# Shield_Master.net
KiCad netlist of a schematic drawn in EAGLE
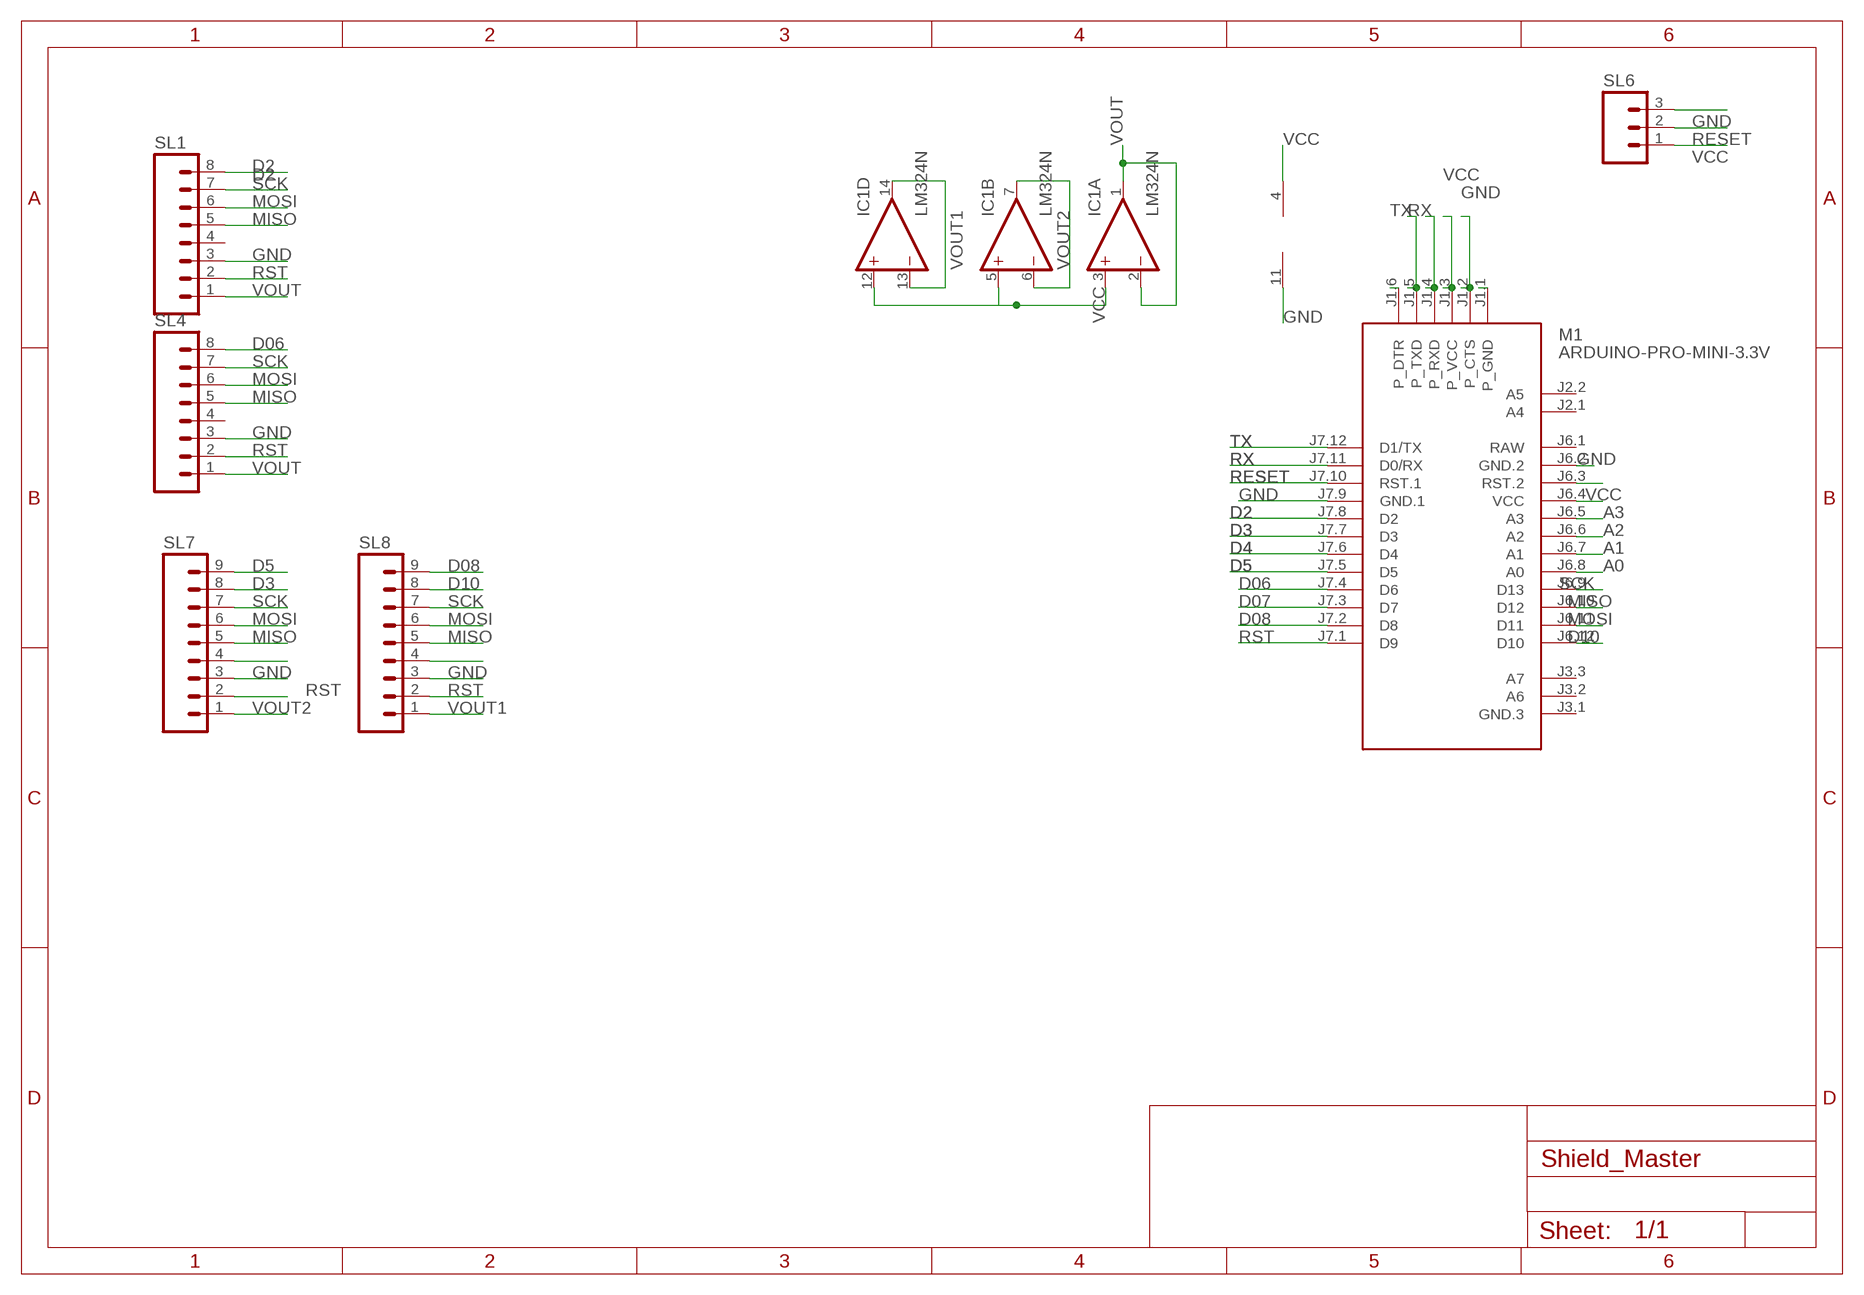
[diagram p0: schematic, sheet 1]

(export (version "E")
  (design (tool "Eeschema 10.0.6"))
  (components
    (comp (ref "IC1")
      (value "LM324N")
      (footprint "eagle-import:DIL14")
      (libsource (lib "eagle-import") (part "LM324N"))
    )
    (comp (ref "M1")
      (value "ARDUINO-PRO-MINI-3.3V")
      (footprint "eagle-import:ARDUINO-PRO-MINI")
      (libsource (lib "eagle-import") (part "ARDUINO-PRO-MINI-3.3V"))
    )
    (comp (ref "SL1")
      (value "M08")
      (footprint "eagle-import:08P")
      (libsource (lib "eagle-import") (part "M08"))
    )
    (comp (ref "SL4")
      (value "M08")
      (footprint "eagle-import:08P")
      (libsource (lib "eagle-import") (part "M08"))
    )
    (comp (ref "SL6")
      (value "M03")
      (footprint "eagle-import:03P")
      (libsource (lib "eagle-import") (part "M03"))
    )
    (comp (ref "SL7")
      (value "M09")
      (footprint "eagle-import:09P")
      (libsource (lib "eagle-import") (part "M09"))
    )
    (comp (ref "SL8")
      (value "M09")
      (footprint "eagle-import:09P")
      (libsource (lib "eagle-import") (part "M09"))
    )
  )
  (nets
    (net (code "1") (name "/A0") (class "Default")
      (node (ref "M1") (pin "J6.8") (pinfunction "A0_J6.8") (pintype "bidirectional"))
    )
    (net (code "2") (name "/A1") (class "Default")
      (node (ref "M1") (pin "J6.7") (pinfunction "A1_J6.7") (pintype "bidirectional"))
    )
    (net (code "3") (name "/A2") (class "Default")
      (node (ref "M1") (pin "J6.6") (pinfunction "A2_J6.6") (pintype "bidirectional"))
    )
    (net (code "4") (name "/A3") (class "Default")
      (node (ref "M1") (pin "J6.5") (pinfunction "A3_J6.5") (pintype "bidirectional"))
    )
    (net (code "5") (name "/D2") (class "Default")
      (node (ref "M1") (pin "J7.8") (pinfunction "D2_J7.8") (pintype "bidirectional"))
      (node (ref "SL1") (pin "8") (pinfunction "8_8") (pintype "passive"))
    )
    (net (code "6") (name "/D3") (class "Default")
      (node (ref "M1") (pin "J7.7") (pinfunction "D3_J7.7") (pintype "bidirectional"))
      (node (ref "SL7") (pin "8") (pinfunction "8_8") (pintype "passive"))
    )
    (net (code "7") (name "/D4") (class "Default")
      (node (ref "M1") (pin "J7.6") (pinfunction "D4_J7.6") (pintype "bidirectional"))
    )
    (net (code "8") (name "/D5") (class "Default")
      (node (ref "M1") (pin "J7.5") (pinfunction "D5_J7.5") (pintype "bidirectional"))
      (node (ref "SL7") (pin "9") (pinfunction "9_9") (pintype "passive"))
    )
    (net (code "9") (name "/D06") (class "Default")
      (node (ref "M1") (pin "J7.4") (pinfunction "D6_J7.4") (pintype "bidirectional"))
      (node (ref "SL4") (pin "8") (pinfunction "8_8") (pintype "passive"))
    )
    (net (code "10") (name "/D07") (class "Default")
      (node (ref "M1") (pin "J7.3") (pinfunction "D7_J7.3") (pintype "bidirectional"))
    )
    (net (code "11") (name "/D08") (class "Default")
      (node (ref "M1") (pin "J7.2") (pinfunction "D8_J7.2") (pintype "bidirectional"))
      (node (ref "SL8") (pin "9") (pinfunction "9_9") (pintype "passive"))
    )
    (net (code "12") (name "/D10") (class "Default")
      (node (ref "M1") (pin "J6.12") (pinfunction "D10_J6.12") (pintype "bidirectional"))
      (node (ref "SL8") (pin "8") (pinfunction "8_8") (pintype "passive"))
    )
    (net (code "13") (name "/GND") (class "Default")
      (node (ref "IC1") (pin "11") (pinfunction "V-_11") (pintype "power_in"))
      (node (ref "M1") (pin "J1.2") (pinfunction "P_CTS_J1.2") (pintype "bidirectional"))
      (node (ref "M1") (pin "J6.2") (pinfunction "GND.2_J6.2") (pintype "power_in"))
      (node (ref "M1") (pin "J7.9") (pinfunction "GND.1_J7.9") (pintype "power_in"))
      (node (ref "SL1") (pin "3") (pinfunction "3_3") (pintype "passive"))
      (node (ref "SL4") (pin "3") (pinfunction "3_3") (pintype "passive"))
      (node (ref "SL6") (pin "3") (pinfunction "3_3") (pintype "passive"))
      (node (ref "SL7") (pin "3") (pinfunction "3_3") (pintype "passive"))
      (node (ref "SL8") (pin "3") (pinfunction "3_3") (pintype "passive"))
    )
    (net (code "14") (name "/MISO") (class "Default")
      (node (ref "M1") (pin "J6.10") (pinfunction "D12_J6.10") (pintype "bidirectional"))
      (node (ref "SL1") (pin "5") (pinfunction "5_5") (pintype "passive"))
      (node (ref "SL4") (pin "5") (pinfunction "5_5") (pintype "passive"))
      (node (ref "SL7") (pin "5") (pinfunction "5_5") (pintype "passive"))
      (node (ref "SL8") (pin "5") (pinfunction "5_5") (pintype "passive"))
    )
    (net (code "15") (name "/MOSI") (class "Default")
      (node (ref "M1") (pin "J6.11") (pinfunction "D11_J6.11") (pintype "bidirectional"))
      (node (ref "SL1") (pin "6") (pinfunction "6_6") (pintype "passive"))
      (node (ref "SL4") (pin "6") (pinfunction "6_6") (pintype "passive"))
      (node (ref "SL7") (pin "6") (pinfunction "6_6") (pintype "passive"))
      (node (ref "SL8") (pin "6") (pinfunction "6_6") (pintype "passive"))
    )
    (net (code "16") (name "/RAW") (class "Default")
      (node (ref "M1") (pin "J6.1") (pinfunction "RAW_J6.1") (pintype "power_in"))
    )
    (net (code "17") (name "/RESET") (class "Default")
      (node (ref "M1") (pin "J7.10") (pinfunction "RST.1_J7.10") (pintype "bidirectional"))
      (node (ref "SL6") (pin "2") (pinfunction "2_2") (pintype "passive"))
    )
    (net (code "18") (name "/RST") (class "Default")
      (node (ref "M1") (pin "J7.1") (pinfunction "D9_J7.1") (pintype "bidirectional"))
      (node (ref "SL1") (pin "2") (pinfunction "2_2") (pintype "passive"))
      (node (ref "SL4") (pin "2") (pinfunction "2_2") (pintype "passive"))
      (node (ref "SL7") (pin "2") (pinfunction "2_2") (pintype "passive"))
      (node (ref "SL8") (pin "2") (pinfunction "2_2") (pintype "passive"))
    )
    (net (code "19") (name "/RX") (class "Default")
      (node (ref "M1") (pin "J1.4") (pinfunction "P_RXD_J1.4") (pintype "bidirectional"))
      (node (ref "M1") (pin "J7.11") (pinfunction "D0/RX_J7.11") (pintype "bidirectional"))
    )
    (net (code "20") (name "/SCK") (class "Default")
      (node (ref "M1") (pin "J6.9") (pinfunction "D13_J6.9") (pintype "bidirectional"))
      (node (ref "SL1") (pin "7") (pinfunction "7_7") (pintype "passive"))
      (node (ref "SL4") (pin "7") (pinfunction "7_7") (pintype "passive"))
      (node (ref "SL7") (pin "7") (pinfunction "7_7") (pintype "passive"))
      (node (ref "SL8") (pin "7") (pinfunction "7_7") (pintype "passive"))
    )
    (net (code "21") (name "/TX") (class "Default")
      (node (ref "M1") (pin "J1.5") (pinfunction "P_TXD_J1.5") (pintype "bidirectional"))
      (node (ref "M1") (pin "J7.12") (pinfunction "D1/TX_J7.12") (pintype "bidirectional"))
    )
    (net (code "22") (name "/VCC") (class "Default")
      (node (ref "IC1") (pin "12") (pinfunction "+IN_12") (pintype "input"))
      (node (ref "IC1") (pin "3") (pinfunction "+IN_3") (pintype "input"))
      (node (ref "IC1") (pin "4") (pinfunction "V+_4") (pintype "power_in"))
      (node (ref "IC1") (pin "5") (pinfunction "+IN_5") (pintype "input"))
      (node (ref "M1") (pin "J1.3") (pinfunction "P_VCC_J1.3") (pintype "bidirectional"))
      (node (ref "M1") (pin "J6.4") (pinfunction "VCC_J6.4") (pintype "power_in"))
      (node (ref "SL6") (pin "1") (pinfunction "1_1") (pintype "passive"))
    )
    (net (code "23") (name "/VOUT") (class "Default")
      (node (ref "IC1") (pin "1") (pinfunction "OUT_1") (pintype "output"))
      (node (ref "IC1") (pin "2") (pinfunction "-IN_2") (pintype "input"))
      (node (ref "SL1") (pin "1") (pinfunction "1_1") (pintype "passive"))
      (node (ref "SL4") (pin "1") (pinfunction "1_1") (pintype "passive"))
    )
    (net (code "24") (name "/VOUT1") (class "Default")
      (node (ref "IC1") (pin "13") (pinfunction "-IN_13") (pintype "input"))
      (node (ref "IC1") (pin "14") (pinfunction "OUT_14") (pintype "output"))
      (node (ref "SL8") (pin "1") (pinfunction "1_1") (pintype "passive"))
    )
    (net (code "25") (name "/VOUT2") (class "Default")
      (node (ref "IC1") (pin "6") (pinfunction "-IN_6") (pintype "input"))
      (node (ref "IC1") (pin "7") (pinfunction "OUT_7") (pintype "output"))
      (node (ref "SL7") (pin "1") (pinfunction "1_1") (pintype "passive"))
    )
    (net (code "26") (name "unconnected-(M1-A4-PadJ2.1)") (class "Default")
      (node (ref "M1") (pin "J2.1") (pinfunction "A4_J2.1") (pintype "bidirectional"))
    )
    (net (code "27") (name "unconnected-(M1-A5-PadJ2.2)") (class "Default")
      (node (ref "M1") (pin "J2.2") (pinfunction "A5_J2.2") (pintype "bidirectional"))
    )
    (net (code "28") (name "unconnected-(M1-A6-PadJ3.2)") (class "Default")
      (node (ref "M1") (pin "J3.2") (pinfunction "A6_J3.2") (pintype "bidirectional"))
    )
    (net (code "29") (name "unconnected-(M1-A7-PadJ3.3)") (class "Default")
      (node (ref "M1") (pin "J3.3") (pinfunction "A7_J3.3") (pintype "bidirectional"))
    )
    (net (code "30") (name "unconnected-(M1-GND.3-PadJ3.1)") (class "Default")
      (node (ref "M1") (pin "J3.1") (pinfunction "GND.3_J3.1") (pintype "bidirectional"))
    )
    (net (code "31") (name "unconnected-(M1-P_DTR-PadJ1.6)") (class "Default")
      (node (ref "M1") (pin "J1.6") (pinfunction "P_DTR_J1.6") (pintype "bidirectional"))
    )
    (net (code "32") (name "unconnected-(M1-P_GND-PadJ1.1)") (class "Default")
      (node (ref "M1") (pin "J1.1") (pinfunction "P_GND_J1.1") (pintype "bidirectional"))
    )
    (net (code "33") (name "unconnected-(M1-RST.2-PadJ6.3)") (class "Default")
      (node (ref "M1") (pin "J6.3") (pinfunction "RST.2_J6.3") (pintype "bidirectional"))
    )
    (net (code "34") (name "unconnected-(SL1-Pad4)") (class "Default")
      (node (ref "SL1") (pin "4") (pinfunction "4_4") (pintype "passive"))
    )
    (net (code "35") (name "unconnected-(SL4-Pad4)") (class "Default")
      (node (ref "SL4") (pin "4") (pinfunction "4_4") (pintype "passive"))
    )
    (net (code "36") (name "unconnected-(SL7-Pad4)") (class "Default")
      (node (ref "SL7") (pin "4") (pinfunction "4_4") (pintype "passive"))
    )
    (net (code "37") (name "unconnected-(SL8-Pad4)") (class "Default")
      (node (ref "SL8") (pin "4") (pinfunction "4_4") (pintype "passive"))
    )
  )
)
